# Smart_Umbrella.net
KiCad netlist of a schematic drawn in Altium Designer
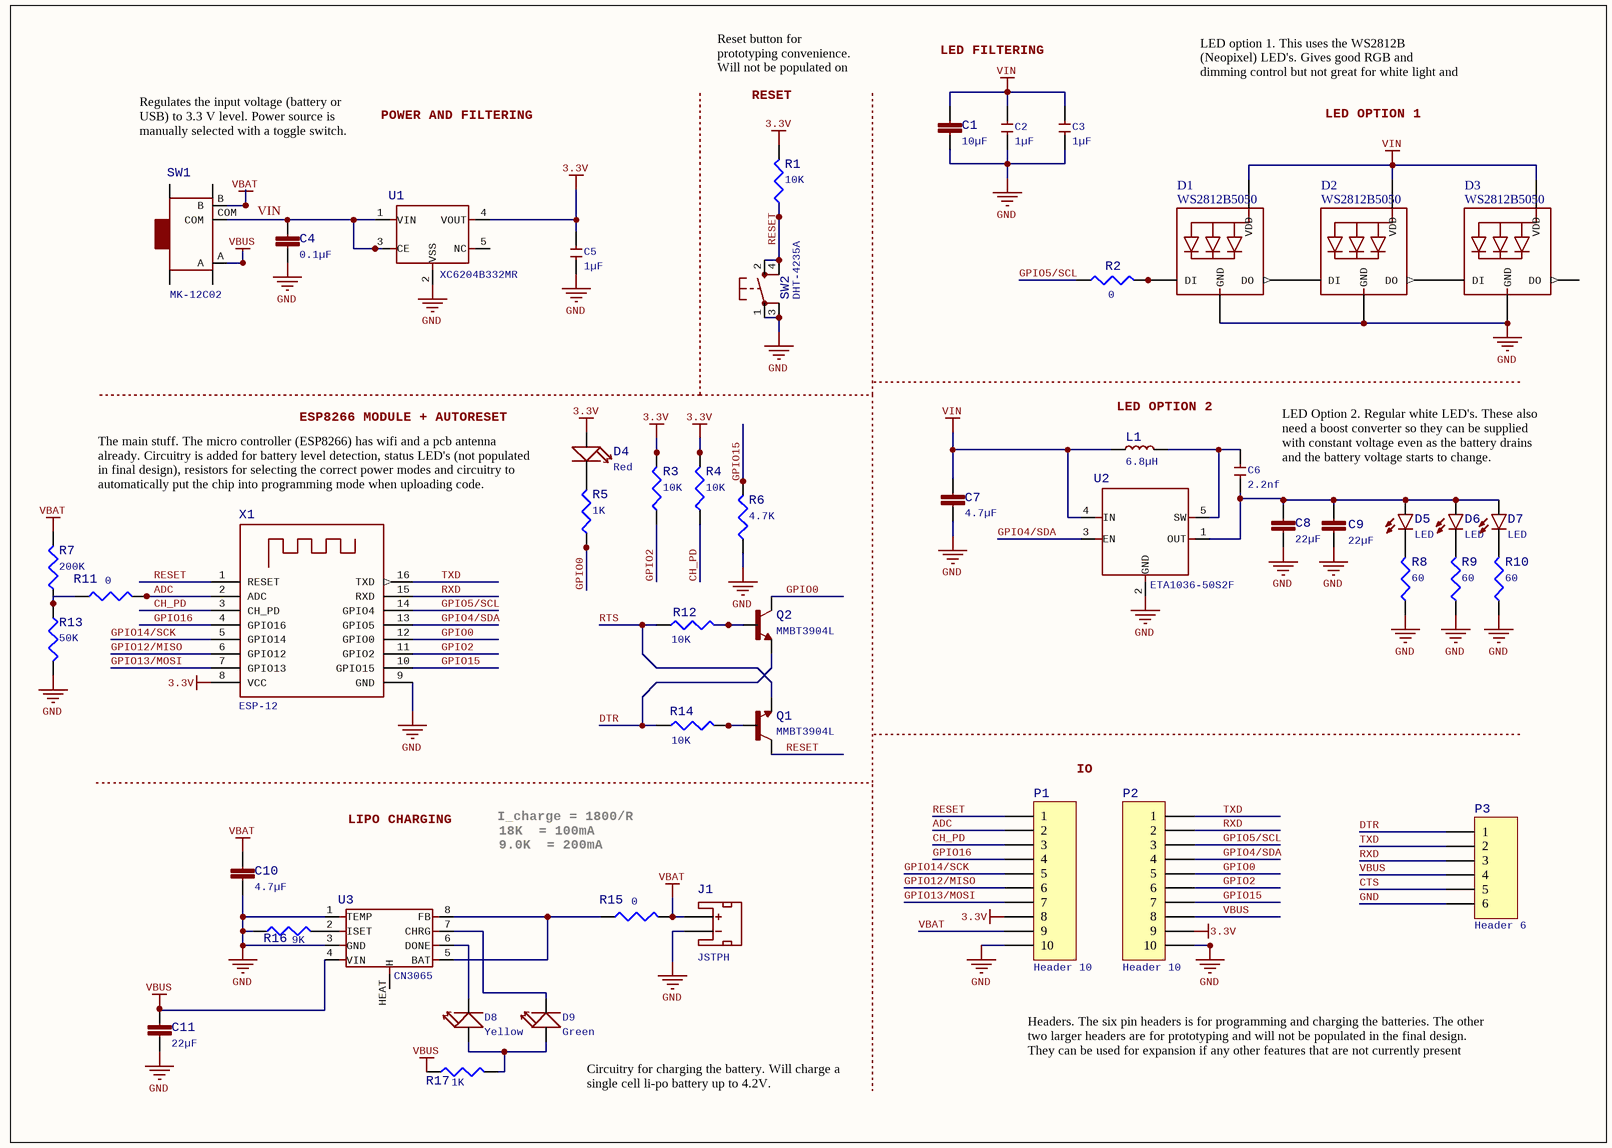
[diagram p0: Smart_Umbrella.SchDoc]

(export (version "E")
  (design (tool "Eeschema 10.0.6"))
  (components
    (comp (ref "C1")
      (value "10µF")
      (footprint "0805")
      (libsource (lib "SparkFun-Capacitors") (part "10UF-0805-10V-10%"))
    )
    (comp (ref "C2")
      (value "1µF")
      (footprint "C0603")
      (fields (field (name "MPN") "CC0603KRX7R8BB105"))
      (libsource (lib "Seeed-OPL-Capacitor") (part "CERAMIC-1UF-25V-10%-X7R(0603)"))
    )
    (comp (ref "C3")
      (value "1µF")
      (footprint "C0603")
      (fields (field (name "MPN") "CC0603KRX7R8BB105"))
      (libsource (lib "Seeed-OPL-Capacitor") (part "CERAMIC-1UF-25V-10%-X7R(0603)"))
    )
    (comp (ref "C4")
      (value "0.1µF")
      (footprint "0805")
      (libsource (lib "SparkFun-Capacitors") (part "10UF-0805-10V-10%"))
    )
    (comp (ref "C5")
      (value "1µF")
      (footprint "C0603")
      (fields (field (name "MPN") "CC0603KRX7R8BB105"))
      (libsource (lib "Seeed-OPL-Capacitor") (part "CERAMIC-1UF-25V-10%-X7R(0603)"))
    )
    (comp (ref "C6")
      (value "2.2nf")
      (footprint "C0603")
      (fields (field (name "MPN") "CC0603KRX7R9BB222"))
      (libsource (lib "Seeed-OPL-Capacitor") (part "CERAMIC-2.2NF-50V-10%-X7R(0603)"))
    )
    (comp (ref "C7")
      (value "4.7µF")
      (footprint "0805")
      (libsource (lib "SparkFun-Capacitors") (part "10UF-0805-10V-10%"))
    )
    (comp (ref "C8")
      (value "22µF")
      (footprint "0805")
      (libsource (lib "SparkFun-Capacitors") (part "10UF-0805-10V-10%"))
    )
    (comp (ref "C9")
      (value "22µF")
      (footprint "0805")
      (libsource (lib "SparkFun-Capacitors") (part "10UF-0805-10V-10%"))
    )
    (comp (ref "C10")
      (value "4.7µF")
      (footprint "0805")
      (libsource (lib "SparkFun-Capacitors") (part "10UF-0805-10V-10%"))
    )
    (comp (ref "C11")
      (value "22µF")
      (footprint "0805")
      (libsource (lib "SparkFun-Capacitors") (part "10UF-0805-10V-10%"))
    )
    (comp (ref "D1")
      (value "WS2812B5050")
      (footprint "WS2812B")
      (libsource (lib "adafruit") (part "WS2812B5050"))
    )
    (comp (ref "D2")
      (value "WS2812B5050")
      (footprint "WS2812B")
      (libsource (lib "adafruit") (part "WS2812B5050"))
    )
    (comp (ref "D3")
      (value "WS2812B5050")
      (footprint "WS2812B")
      (libsource (lib "adafruit") (part "WS2812B5050"))
    )
    (comp (ref "D4") (value "Red") (footprint "LED-0603") (libsource (lib "Discrete") (part "LED-0603")))
    (comp (ref "D5") (value "LED") (footprint "LED_5MM") (libsource (lib "SparkFun-LED") (part "LED5MM")))
    (comp (ref "D6") (value "LED") (footprint "LED_5MM") (libsource (lib "SparkFun-LED") (part "LED5MM")))
    (comp (ref "D7") (value "LED") (footprint "LED_5MM") (libsource (lib "SparkFun-LED") (part "LED5MM")))
    (comp (ref "D8")
      (value "Yellow")
      (footprint "LED-0603")
      (fields (field (name "MPN") "19-217-Y5C-AM1N1VY-3T"))
      (libsource (lib "Seeed-OPL-Diode") (part "SMD-LED-CLEAR-YELLOW(0603)"))
    )
    (comp (ref "D9")
      (value "Green")
      (footprint "LED-0603")
      (fields (field (name "MPN") "19-217-G7C-AN1P2-3T"))
      (libsource (lib "Seeed-OPL-Diode") (part "SMD-LED-CLEAR-GREEN(0603)"))
    )
    (comp (ref "J1")
      (value "JSTPH")
      (footprint "JST-2-SMD")
      (libsource (lib "SparkFun-Connectors") (part "JST_2MM_MALE"))
    )
    (comp (ref "L1")
      (value "6.8µH")
      (footprint "L0603")
      (libsource (lib "Discrete") (part "INDUCTOR/FERRITE-BEAD-0603"))
    )
    (comp (ref "P1")
      (value "Header 10")
      (footprint "HDR1X10")
      (description "Header, 10-Pin")
      (fields (field (name "PUBLISHER") "Altium Limited"))
      (libsource (lib "") (part "Header 10_1"))
    )
    (comp (ref "P2")
      (value "Header 10")
      (footprint "HDR1X10")
      (description "Header, 10-Pin")
      (fields (field (name "PUBLISHER") "Altium Limited"))
      (libsource (lib "Miscellaneous Connectors") (part "Header 10"))
    )
    (comp (ref "P3")
      (value "Header 6")
      (footprint "HDR1X6")
      (description "Header, 6-Pin")
      (fields (field (name "PUBLISHER") "Altium Limited"))
      (libsource (lib "Miscellaneous Connectors") (part "Header 6"))
    )
    (comp (ref "Q1")
      (value "MMBT3904L")
      (footprint "SOT23-3")
      (fields (field (name "DRAWN") "KTOWN"))
      (libsource (lib "") (part "TRANSISTOR_NPNSOT23-3_1"))
    )
    (comp (ref "Q2")
      (value "MMBT3904L")
      (footprint "SOT23-3")
      (fields (field (name "DRAWN") "KTOWN"))
      (libsource (lib "SparkFun") (part "TRANSISTOR_NPNSOT23-3"))
    )
    (comp (ref "R1")
      (value "10K")
      (footprint "J1-0603")
      (description "Resistor")
      (fields (field (name "Comment") "Res3") (field (name "PUBLISHER") "Altium Limited"))
      (libsource (lib "Miscellaneous Devices") (part "Res3"))
    )
    (comp (ref "R2")
      (value "0")
      (footprint "J1-0603")
      (description "Resistor")
      (fields (field (name "Comment") "Res3") (field (name "PUBLISHER") "Altium Limited"))
      (libsource (lib "Miscellaneous Devices") (part "Res3"))
    )
    (comp (ref "R3")
      (value "10K")
      (footprint "J1-0603")
      (description "Resistor")
      (fields (field (name "Comment") "Res3") (field (name "PUBLISHER") "Altium Limited"))
      (libsource (lib "Miscellaneous Devices") (part "Res3"))
    )
    (comp (ref "R4")
      (value "10K")
      (footprint "J1-0603")
      (description "Resistor")
      (fields (field (name "Comment") "Res3") (field (name "PUBLISHER") "Altium Limited"))
      (libsource (lib "Miscellaneous Devices") (part "Res3"))
    )
    (comp (ref "R5")
      (value "1K")
      (footprint "J1-0603")
      (description "Resistor")
      (fields (field (name "Comment") "Res3") (field (name "PUBLISHER") "Altium Limited"))
      (libsource (lib "Miscellaneous Devices") (part "Res3"))
    )
    (comp (ref "R6")
      (value "4.7K")
      (footprint "J1-0603")
      (description "Resistor")
      (fields (field (name "Comment") "Res3") (field (name "PUBLISHER") "Altium Limited"))
      (libsource (lib "Miscellaneous Devices") (part "Res3"))
    )
    (comp (ref "R7")
      (value "200K")
      (footprint "J1-0603")
      (description "Resistor")
      (fields (field (name "Comment") "Res3") (field (name "PUBLISHER") "Altium Limited"))
      (libsource (lib "Miscellaneous Devices") (part "Res3"))
    )
    (comp (ref "R8")
      (value "60")
      (footprint "J1-0603")
      (description "Resistor")
      (fields (field (name "Comment") "Res3") (field (name "PUBLISHER") "Altium Limited"))
      (libsource (lib "Miscellaneous Devices") (part "Res3"))
    )
    (comp (ref "R9")
      (value "60")
      (footprint "J1-0603")
      (description "Resistor")
      (fields (field (name "Comment") "Res3") (field (name "PUBLISHER") "Altium Limited"))
      (libsource (lib "Miscellaneous Devices") (part "Res3"))
    )
    (comp (ref "R10")
      (value "60")
      (footprint "J1-0603")
      (description "Resistor")
      (fields (field (name "Comment") "Res3") (field (name "PUBLISHER") "Altium Limited"))
      (libsource (lib "Miscellaneous Devices") (part "Res3"))
    )
    (comp (ref "R11")
      (value "0")
      (footprint "J1-0603")
      (description "Resistor")
      (fields (field (name "Comment") "Res3") (field (name "PUBLISHER") "Altium Limited"))
      (libsource (lib "Miscellaneous Devices") (part "Res3"))
    )
    (comp (ref "R12")
      (value "10K")
      (footprint "J1-0603")
      (description "Resistor")
      (fields (field (name "Comment") "Res3") (field (name "PUBLISHER") "Altium Limited"))
      (libsource (lib "Miscellaneous Devices") (part "Res3"))
    )
    (comp (ref "R13")
      (value "50K")
      (footprint "J1-0603")
      (description "Resistor")
      (fields (field (name "Comment") "Res3") (field (name "PUBLISHER") "Altium Limited"))
      (libsource (lib "Miscellaneous Devices") (part "Res3"))
    )
    (comp (ref "R14")
      (value "10K")
      (footprint "J1-0603")
      (description "Resistor")
      (fields (field (name "Comment") "Res3") (field (name "PUBLISHER") "Altium Limited"))
      (libsource (lib "Miscellaneous Devices") (part "Res3"))
    )
    (comp (ref "R15")
      (value "0")
      (footprint "J1-0603")
      (description "Resistor")
      (fields (field (name "Comment") "Res3") (field (name "PUBLISHER") "Altium Limited"))
      (libsource (lib "Miscellaneous Devices") (part "Res3"))
    )
    (comp (ref "R16")
      (value "9K")
      (footprint "J1-0603")
      (description "Resistor")
      (fields (field (name "Comment") "Res3") (field (name "PUBLISHER") "Altium Limited"))
      (libsource (lib "Miscellaneous Devices") (part "Res3"))
    )
    (comp (ref "R17")
      (value "1K")
      (footprint "J1-0603")
      (description "Resistor")
      (fields (field (name "Comment") "Res3") (field (name "PUBLISHER") "Altium Limited"))
      (libsource (lib "Miscellaneous Devices") (part "Res3"))
    )
    (comp (ref "SW1")
      (value "MK-12C02")
      (footprint "SW7-SMD-L6.7X2.7X3.2MM")
      (libsource (lib "Seeed-OPL-Button") (part "SMD-TOGGLE-SWITCH-ON-ON(3+4P-6.7X2.7MM)"))
    )
    (comp (ref "SW2")
      (value "DHT-4235A")
      (footprint "KMR2")
      (libsource (lib "adafruit") (part "SPST_TACT-KMR2"))
    )
    (comp (ref "U1")
      (value "XC6204B332MR")
      (footprint "SOT-23-5")
      (libsource (lib "Seeed-OPL-ic") (part "PMIC-LDO-XC6204B332MR(SOT23-5)"))
    )
    (comp (ref "U2")
      (value "ETA1036-50S2F")
      (footprint "SOT-23-5")
      (fields (field (name "MPN") "ETA1036-50S2F-T"))
      (libsource (lib "Seeed-OPL-ic") (part "PMIC-ETA1036-50S2F-T(SOT23-5)"))
    )
    (comp (ref "U3")
      (value "CN3065")
      (footprint "DFN8G-0.5-3X3MM")
      (libsource (lib "Seeed-OPL-ic") (part "PMIC-CN3065(DFN8)"))
    )
    (comp (ref "X1") (value "ESP-12") (footprint "ESP-12") (libsource (lib "adafruit") (part "ESP-12")))
  )
  (nets
    (net (code "1") (name "/ADC") (class "Default")
      (node (ref "P1") (pin "2") (pinfunction "2_2") (pintype "passive"))
      (node (ref "R11") (pin "2") (pinfunction "2_2") (pintype "passive"))
      (node (ref "X1") (pin "2") (pinfunction "ADC_2") (pintype "passive"))
    )
    (net (code "2") (name "/CH_PD") (class "Default")
      (node (ref "P1") (pin "3") (pinfunction "3_3") (pintype "passive"))
      (node (ref "R4") (pin "1") (pinfunction "1_1") (pintype "passive"))
      (node (ref "X1") (pin "3") (pinfunction "CH_PD_3") (pintype "passive"))
    )
    (net (code "3") (name "/CTS") (class "Default")
      (node (ref "P3") (pin "5") (pinfunction "5_5") (pintype "passive"))
    )
    (net (code "4") (name "/DTR") (class "Default")
      (node (ref "P3") (pin "1") (pinfunction "1_1") (pintype "passive"))
      (node (ref "Q2") (pin "2") (pinfunction "E_2") (pintype "passive"))
      (node (ref "R14") (pin "1") (pinfunction "1_1") (pintype "passive"))
    )
    (net (code "5") (name "/GPIO0") (class "Default")
      (node (ref "P2") (pin "5") (pinfunction "5_5") (pintype "passive"))
      (node (ref "Q2") (pin "3") (pinfunction "C_3") (pintype "passive"))
      (node (ref "R5") (pin "1") (pinfunction "1_1") (pintype "passive"))
      (node (ref "X1") (pin "12") (pinfunction "GPIO0_12") (pintype "passive"))
    )
    (net (code "6") (name "/GPIO2") (class "Default")
      (node (ref "P2") (pin "6") (pinfunction "6_6") (pintype "passive"))
      (node (ref "R3") (pin "1") (pinfunction "1_1") (pintype "passive"))
      (node (ref "X1") (pin "11") (pinfunction "GPIO2_11") (pintype "passive"))
    )
    (net (code "7") (name "/GPIO4{slash}SDA") (class "Default")
      (node (ref "P2") (pin "4") (pinfunction "4_4") (pintype "passive"))
      (node (ref "U2") (pin "3") (pinfunction "EN_3") (pintype "passive"))
      (node (ref "X1") (pin "13") (pinfunction "GPIO5_13") (pintype "passive"))
    )
    (net (code "8") (name "/GPIO5{slash}SCL") (class "Default")
      (node (ref "P2") (pin "3") (pinfunction "3_3") (pintype "passive"))
      (node (ref "R2") (pin "1") (pinfunction "1_1") (pintype "passive"))
      (node (ref "X1") (pin "14") (pinfunction "GPIO4_14") (pintype "passive"))
    )
    (net (code "9") (name "/GPIO12{slash}MISO") (class "Default")
      (node (ref "P1") (pin "6") (pinfunction "6_6") (pintype "passive"))
      (node (ref "X1") (pin "6") (pinfunction "GPIO12_6") (pintype "passive"))
    )
    (net (code "10") (name "/GPIO13{slash}MOSI") (class "Default")
      (node (ref "P1") (pin "7") (pinfunction "7_7") (pintype "passive"))
      (node (ref "X1") (pin "7") (pinfunction "GPIO13_7") (pintype "passive"))
    )
    (net (code "11") (name "/GPIO14{slash}SCK") (class "Default")
      (node (ref "P1") (pin "5") (pinfunction "5_5") (pintype "passive"))
      (node (ref "X1") (pin "5") (pinfunction "GPIO14_5") (pintype "passive"))
    )
    (net (code "12") (name "/GPIO15") (class "Default")
      (node (ref "P2") (pin "7") (pinfunction "7_7") (pintype "passive"))
      (node (ref "R6") (pin "2") (pinfunction "2_2") (pintype "passive"))
      (node (ref "X1") (pin "10") (pinfunction "GPIO15_10") (pintype "passive"))
    )
    (net (code "13") (name "/GPIO16") (class "Default")
      (node (ref "P1") (pin "4") (pinfunction "4_4") (pintype "passive"))
      (node (ref "X1") (pin "4") (pinfunction "GPIO16_4") (pintype "passive"))
    )
    (net (code "14") (name "/RESET") (class "Default")
      (node (ref "P1") (pin "1") (pinfunction "1_1") (pintype "passive"))
      (node (ref "Q1") (pin "3") (pinfunction "C_3") (pintype "passive"))
      (node (ref "R1") (pin "1") (pinfunction "1_1") (pintype "passive"))
      (node (ref "SW2") (pin "2") (pinfunction "S_2") (pintype "passive"))
      (node (ref "SW2") (pin "4") (pinfunction "S1_4") (pintype "passive"))
      (node (ref "X1") (pin "1") (pinfunction "RESET_1") (pintype "passive"))
    )
    (net (code "15") (name "/RTS") (class "Default")
      (node (ref "Q1") (pin "2") (pinfunction "E_2") (pintype "passive"))
      (node (ref "R12") (pin "1") (pinfunction "1_1") (pintype "passive"))
    )
    (net (code "16") (name "/RXD") (class "Default")
      (node (ref "P2") (pin "2") (pinfunction "2_2") (pintype "passive"))
      (node (ref "P3") (pin "3") (pinfunction "3_3") (pintype "passive"))
      (node (ref "X1") (pin "15") (pinfunction "RXD_15") (pintype "passive"))
    )
    (net (code "17") (name "/TXD") (class "Default")
      (node (ref "P2") (pin "1") (pinfunction "1_1") (pintype "passive"))
      (node (ref "P3") (pin "2") (pinfunction "2_2") (pintype "passive"))
      (node (ref "X1") (pin "16") (pinfunction "TXD_16") (pintype "output"))
    )
    (net (code "18") (name "3.3V") (class "Default")
      (node (ref "C5") (pin "2") (pinfunction "2_2") (pintype "passive"))
      (node (ref "D4") (pin "+") (pinfunction "+_+") (pintype "passive"))
      (node (ref "P1") (pin "8") (pinfunction "8_8") (pintype "passive"))
      (node (ref "P2") (pin "9") (pinfunction "9_9") (pintype "passive"))
      (node (ref "R1") (pin "2") (pinfunction "2_2") (pintype "passive"))
      (node (ref "R3") (pin "2") (pinfunction "2_2") (pintype "passive"))
      (node (ref "R4") (pin "2") (pinfunction "2_2") (pintype "passive"))
      (node (ref "U1") (pin "4") (pinfunction "VOUT_4") (pintype "power_in"))
      (node (ref "X1") (pin "8") (pinfunction "VCC_8") (pintype "power_in"))
    )
    (net (code "19") (name "GND") (class "Default")
      (node (ref "C1") (pin "2") (pinfunction "2_2") (pintype "passive"))
      (node (ref "C10") (pin "2") (pinfunction "2_2") (pintype "passive"))
      (node (ref "C11") (pin "2") (pinfunction "2_2") (pintype "passive"))
      (node (ref "C2") (pin "1") (pinfunction "1_1") (pintype "passive"))
      (node (ref "C3") (pin "1") (pinfunction "1_1") (pintype "passive"))
      (node (ref "C4") (pin "2") (pinfunction "2_2") (pintype "passive"))
      (node (ref "C5") (pin "1") (pinfunction "1_1") (pintype "passive"))
      (node (ref "C7") (pin "2") (pinfunction "2_2") (pintype "passive"))
      (node (ref "C8") (pin "2") (pinfunction "2_2") (pintype "passive"))
      (node (ref "C9") (pin "2") (pinfunction "2_2") (pintype "passive"))
      (node (ref "D1") (pin "3") (pinfunction "GND_3") (pintype "power_in"))
      (node (ref "D2") (pin "3") (pinfunction "GND_3") (pintype "power_in"))
      (node (ref "D3") (pin "3") (pinfunction "GND_3") (pintype "power_in"))
      (node (ref "J1") (pin "1") (pinfunction "-_1") (pintype "passive"))
      (node (ref "P1") (pin "10") (pinfunction "10_10") (pintype "passive"))
      (node (ref "P2") (pin "10") (pinfunction "10_10") (pintype "passive"))
      (node (ref "P3") (pin "6") (pinfunction "6_6") (pintype "passive"))
      (node (ref "R10") (pin "1") (pinfunction "1_1") (pintype "passive"))
      (node (ref "R13") (pin "2") (pinfunction "2_2") (pintype "passive"))
      (node (ref "R16") (pin "1") (pinfunction "1_1") (pintype "passive"))
      (node (ref "R6") (pin "1") (pinfunction "1_1") (pintype "passive"))
      (node (ref "R8") (pin "1") (pinfunction "1_1") (pintype "passive"))
      (node (ref "R9") (pin "1") (pinfunction "1_1") (pintype "passive"))
      (node (ref "SW2") (pin "1") (pinfunction "P_1") (pintype "passive"))
      (node (ref "SW2") (pin "3") (pinfunction "P1_3") (pintype "passive"))
      (node (ref "U1") (pin "2") (pinfunction "VSS_2") (pintype "power_in"))
      (node (ref "U2") (pin "2") (pinfunction "GND_2") (pintype "passive"))
      (node (ref "U3") (pin "1") (pinfunction "TEMP_1") (pintype "passive"))
      (node (ref "U3") (pin "3") (pinfunction "GND_3") (pintype "power_in"))
      (node (ref "X1") (pin "9") (pinfunction "GND_9") (pintype "power_in"))
    )
    (net (code "20") (name "Net-(D1-DI)") (class "Default")
      (node (ref "D1") (pin "4") (pinfunction "DI_4") (pintype "passive"))
      (node (ref "R2") (pin "2") (pinfunction "2_2") (pintype "passive"))
    )
    (net (code "21") (name "Net-(D1-DO)") (class "Default")
      (node (ref "D1") (pin "2") (pinfunction "DO_2") (pintype "output"))
      (node (ref "D2") (pin "4") (pinfunction "DI_4") (pintype "passive"))
    )
    (net (code "22") (name "Net-(D2-DO)") (class "Default")
      (node (ref "D2") (pin "2") (pinfunction "DO_2") (pintype "output"))
      (node (ref "D3") (pin "4") (pinfunction "DI_4") (pintype "passive"))
    )
    (net (code "23") (name "Net-(D4-Pad-)") (class "Default")
      (node (ref "D4") (pin "-") (pinfunction "-_-") (pintype "passive"))
      (node (ref "R5") (pin "2") (pinfunction "2_2") (pintype "passive"))
    )
    (net (code "24") (name "Net-(D5-C)") (class "Default")
      (node (ref "D5") (pin "K") (pinfunction "C_K") (pintype "passive"))
      (node (ref "R8") (pin "2") (pinfunction "2_2") (pintype "passive"))
    )
    (net (code "25") (name "Net-(D6-C)") (class "Default")
      (node (ref "D6") (pin "K") (pinfunction "C_K") (pintype "passive"))
      (node (ref "R9") (pin "2") (pinfunction "2_2") (pintype "passive"))
    )
    (net (code "26") (name "Net-(D7-C)") (class "Default")
      (node (ref "D7") (pin "K") (pinfunction "C_K") (pintype "passive"))
      (node (ref "R10") (pin "2") (pinfunction "2_2") (pintype "passive"))
    )
    (net (code "27") (name "Net-(D8-Pad+)") (class "Default")
      (node (ref "D8") (pin "+") (pinfunction "+_+") (pintype "passive"))
      (node (ref "D9") (pin "+") (pinfunction "+_+") (pintype "passive"))
      (node (ref "R17") (pin "2") (pinfunction "2_2") (pintype "passive"))
    )
    (net (code "28") (name "Net-(Q1-B)") (class "Default")
      (node (ref "Q1") (pin "1") (pinfunction "B_1") (pintype "passive"))
      (node (ref "R14") (pin "2") (pinfunction "2_2") (pintype "passive"))
    )
    (net (code "29") (name "Net-(Q2-B)") (class "Default")
      (node (ref "Q2") (pin "1") (pinfunction "B_1") (pintype "passive"))
      (node (ref "R12") (pin "2") (pinfunction "2_2") (pintype "passive"))
    )
    (net (code "30") (name "Net-(R11-Pad1)") (class "Default")
      (node (ref "R11") (pin "1") (pinfunction "1_1") (pintype "passive"))
      (node (ref "R13") (pin "1") (pinfunction "1_1") (pintype "passive"))
      (node (ref "R7") (pin "1") (pinfunction "1_1") (pintype "passive"))
    )
    (net (code "31") (name "Net-(U2-OUT)") (class "Default")
      (node (ref "C6") (pin "1") (pinfunction "1_1") (pintype "passive"))
      (node (ref "C8") (pin "1") (pinfunction "1_1") (pintype "passive"))
      (node (ref "C9") (pin "1") (pinfunction "1_1") (pintype "passive"))
      (node (ref "D5") (pin "A") (pinfunction "A_A") (pintype "passive"))
      (node (ref "D6") (pin "A") (pinfunction "A_A") (pintype "passive"))
      (node (ref "D7") (pin "A") (pinfunction "A_A") (pintype "passive"))
      (node (ref "U2") (pin "1") (pinfunction "OUT_1") (pintype "passive"))
    )
    (net (code "32") (name "Net-(U2-SW)") (class "Default")
      (node (ref "C6") (pin "2") (pinfunction "2_2") (pintype "passive"))
      (node (ref "L1") (pin "2") (pinfunction "2_2") (pintype "passive"))
      (node (ref "U2") (pin "5") (pinfunction "SW_5") (pintype "passive"))
    )
    (net (code "33") (name "Net-(U3-BAT)") (class "Default")
      (node (ref "R15") (pin "1") (pinfunction "1_1") (pintype "passive"))
      (node (ref "U3") (pin "5") (pinfunction "BAT_5") (pintype "passive"))
      (node (ref "U3") (pin "8") (pinfunction "FB_8") (pintype "passive"))
    )
    (net (code "34") (name "Net-(U3-CHRG)") (class "Default")
      (node (ref "D9") (pin "-") (pinfunction "-_-") (pintype "passive"))
      (node (ref "U3") (pin "7") (pinfunction "CHRG_7") (pintype "passive"))
    )
    (net (code "35") (name "Net-(U3-DONE)") (class "Default")
      (node (ref "D8") (pin "-") (pinfunction "-_-") (pintype "passive"))
      (node (ref "U3") (pin "6") (pinfunction "DONE_6") (pintype "passive"))
    )
    (net (code "36") (name "Net-(U3-ISET)") (class "Default")
      (node (ref "R16") (pin "2") (pinfunction "2_2") (pintype "passive"))
      (node (ref "U3") (pin "2") (pinfunction "ISET_2") (pintype "passive"))
    )
    (net (code "37") (name "VBAT") (class "Default")
      (node (ref "C10") (pin "1") (pinfunction "1_1") (pintype "passive"))
      (node (ref "J1") (pin "2") (pinfunction "+_2") (pintype "passive"))
      (node (ref "P1") (pin "9") (pinfunction "9_9") (pintype "passive"))
      (node (ref "R15") (pin "2") (pinfunction "2_2") (pintype "passive"))
      (node (ref "R7") (pin "2") (pinfunction "2_2") (pintype "passive"))
      (node (ref "SW1") (pin "B") (pinfunction "B_B") (pintype "passive"))
    )
    (net (code "38") (name "VBUS") (class "Default")
      (node (ref "C11") (pin "1") (pinfunction "1_1") (pintype "passive"))
      (node (ref "P2") (pin "8") (pinfunction "8_8") (pintype "passive"))
      (node (ref "P3") (pin "4") (pinfunction "4_4") (pintype "passive"))
      (node (ref "R17") (pin "1") (pinfunction "1_1") (pintype "passive"))
      (node (ref "SW1") (pin "A") (pinfunction "A_A") (pintype "passive"))
      (node (ref "U3") (pin "4") (pinfunction "VIN_4") (pintype "passive"))
    )
    (net (code "39") (name "VIN") (class "Default")
      (node (ref "C1") (pin "1") (pinfunction "1_1") (pintype "passive"))
      (node (ref "C2") (pin "2") (pinfunction "2_2") (pintype "passive"))
      (node (ref "C3") (pin "2") (pinfunction "2_2") (pintype "passive"))
      (node (ref "C4") (pin "1") (pinfunction "1_1") (pintype "passive"))
      (node (ref "C7") (pin "1") (pinfunction "1_1") (pintype "passive"))
      (node (ref "D1") (pin "1") (pinfunction "VDD_1") (pintype "power_in"))
      (node (ref "D2") (pin "1") (pinfunction "VDD_1") (pintype "power_in"))
      (node (ref "D3") (pin "1") (pinfunction "VDD_1") (pintype "power_in"))
      (node (ref "L1") (pin "1") (pinfunction "1_1") (pintype "passive"))
      (node (ref "SW1") (pin "COM") (pinfunction "COM_COM") (pintype "passive"))
      (node (ref "U1") (pin "1") (pinfunction "VIN_1") (pintype "passive"))
      (node (ref "U1") (pin "3") (pinfunction "CE_3") (pintype "passive"))
      (node (ref "U2") (pin "4") (pinfunction "IN_4") (pintype "passive"))
    )
    (net (code "40") (name "unconnected-(D3-DO-Pad2)") (class "Default")
      (node (ref "D3") (pin "2") (pinfunction "DO_2") (pintype "output"))
    )
    (net (code "41") (name "unconnected-(J1-PAD1-PadNC1)") (class "Default")
      (node (ref "J1") (pin "NC1") (pinfunction "PAD1_NC1") (pintype "passive"))
    )
    (net (code "42") (name "unconnected-(J1-PAD2-PadNC2)") (class "Default")
      (node (ref "J1") (pin "NC2") (pinfunction "PAD2_NC2") (pintype "passive"))
    )
    (net (code "43") (name "unconnected-(SW1-PadSS1)") (class "Default")
      (node (ref "SW1") (pin "SS1") (pinfunction "SS1_SS1") (pintype "passive"))
    )
    (net (code "44") (name "unconnected-(SW1-PadSS2)") (class "Default")
      (node (ref "SW1") (pin "SS2") (pinfunction "SS2_SS2") (pintype "passive"))
    )
    (net (code "45") (name "unconnected-(SW1-PadSS3)") (class "Default")
      (node (ref "SW1") (pin "SS3") (pinfunction "SS3_SS3") (pintype "passive"))
    )
    (net (code "46") (name "unconnected-(SW1-PadSS4)") (class "Default")
      (node (ref "SW1") (pin "SS4") (pinfunction "SS4_SS4") (pintype "passive"))
    )
    (net (code "47") (name "unconnected-(U1-NC-Pad5)") (class "Default")
      (node (ref "U1") (pin "5") (pinfunction "NC_5") (pintype "passive"))
    )
    (net (code "48") (name "unconnected-(U3-H-PadHEAT)") (class "Default")
      (node (ref "U3") (pin "HEAT") (pinfunction "H_HEAT") (pintype "passive"))
    )
  )
)
